# untitled.net
KiCad netlist of a schematic drawn in EAGLE
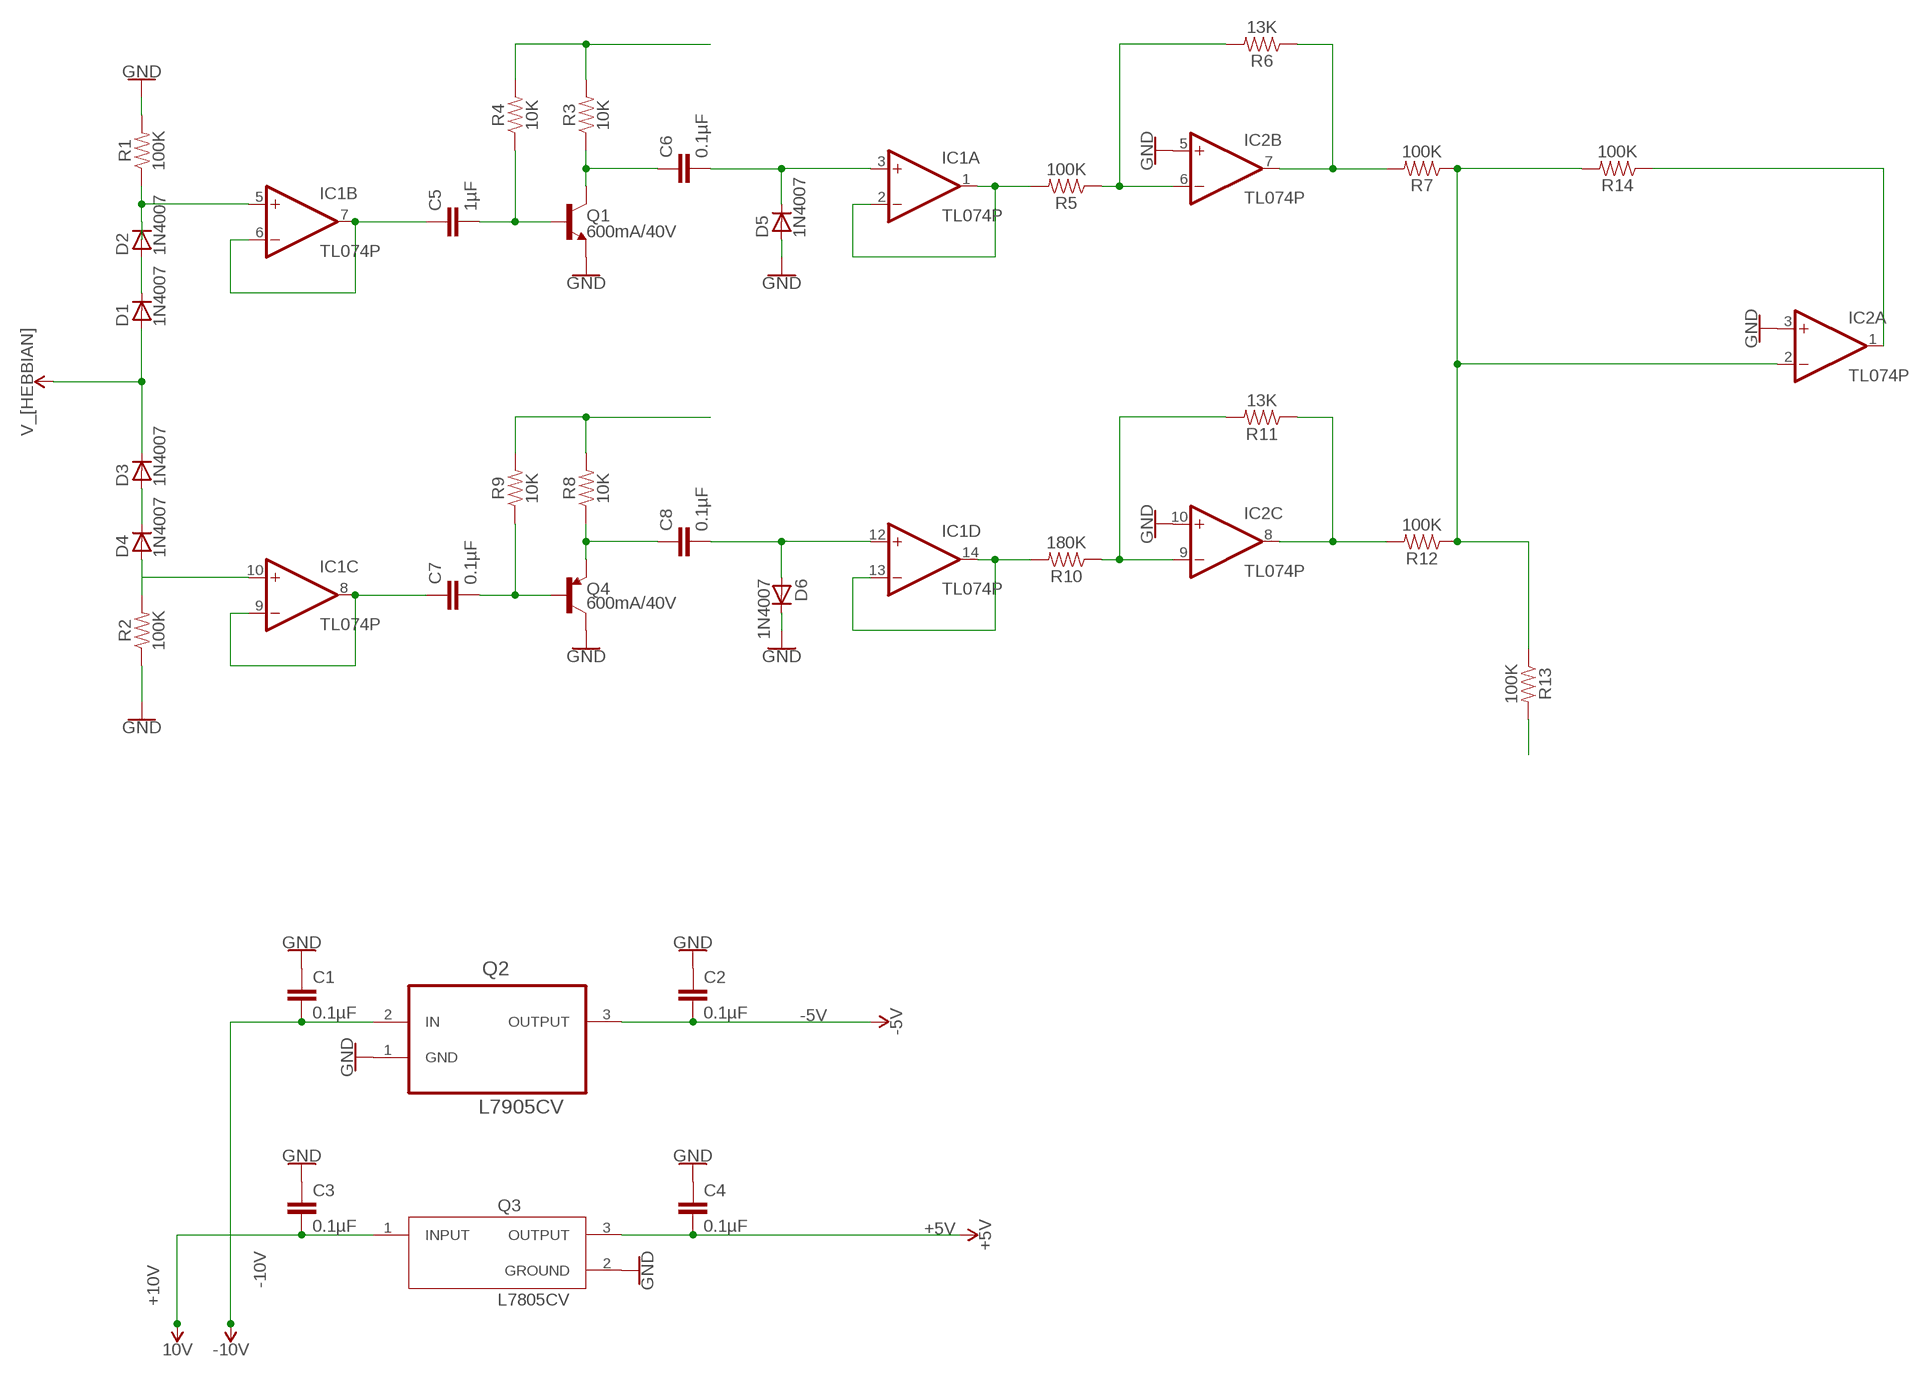
[diagram p0: schematic, sheet 1]

(export (version "E")
  (design (tool "Eeschema 10.0.6"))
  (components
    (comp (ref "C1")
      (value "0.1µF")
      (footprint "eagle-import:0805")
      (libsource (lib "eagle-import") (part "0.33UF/330NF-0805-50V-10%"))
    )
    (comp (ref "C2")
      (value "0.1µF")
      (footprint "eagle-import:0805")
      (libsource (lib "eagle-import") (part "0.33UF/330NF-0805-50V-10%"))
    )
    (comp (ref "C3")
      (value "0.1µF")
      (footprint "eagle-import:0805")
      (libsource (lib "eagle-import") (part "0.33UF/330NF-0805-50V-10%"))
    )
    (comp (ref "C4")
      (value "0.1µF")
      (footprint "eagle-import:0805")
      (libsource (lib "eagle-import") (part "0.33UF/330NF-0805-50V-10%"))
    )
    (comp (ref "C5")
      (value "1µF")
      (footprint "eagle-import:0805")
      (libsource (lib "eagle-import") (part "0.33UF/330NF-0805-50V-10%"))
    )
    (comp (ref "C6")
      (value "0.1µF")
      (footprint "eagle-import:0805")
      (libsource (lib "eagle-import") (part "0.33UF/330NF-0805-50V-10%"))
    )
    (comp (ref "C7")
      (value "0.1µF")
      (footprint "eagle-import:0805")
      (libsource (lib "eagle-import") (part "0.33UF/330NF-0805-50V-10%"))
    )
    (comp (ref "C8")
      (value "0.1µF")
      (footprint "eagle-import:0805")
      (libsource (lib "eagle-import") (part "0.33UF/330NF-0805-50V-10%"))
    )
    (comp (ref "D1")
      (value "1N4007")
      (footprint "eagle-import:SMA")
      (libsource (lib "eagle-import") (part "1N4007"))
    )
    (comp (ref "D2")
      (value "1N4007")
      (footprint "eagle-import:SMA")
      (libsource (lib "eagle-import") (part "1N4007"))
    )
    (comp (ref "D3")
      (value "1N4007")
      (footprint "eagle-import:SMA")
      (libsource (lib "eagle-import") (part "1N4007"))
    )
    (comp (ref "D4")
      (value "1N4007")
      (footprint "eagle-import:SMA")
      (libsource (lib "eagle-import") (part "1N4007"))
    )
    (comp (ref "D5")
      (value "1N4007")
      (footprint "eagle-import:SMA")
      (libsource (lib "eagle-import") (part "1N4007"))
    )
    (comp (ref "D6")
      (value "1N4007")
      (footprint "eagle-import:SMA")
      (libsource (lib "eagle-import") (part "1N4007"))
    )
    (comp (ref "IC1")
      (value "TL074P")
      (footprint "eagle-import:DIL14")
      (libsource (lib "eagle-import") (part "TL074P"))
    )
    (comp (ref "IC2")
      (value "TL074P")
      (footprint "eagle-import:DIL14")
      (libsource (lib "eagle-import") (part "TL074P"))
    )
    (comp (ref "Q1")
      (value "600mA/40V")
      (footprint "eagle-import:SOT23-3")
      (libsource (lib "eagle-import") (part "TRANS_NPN-MMBT2222AL"))
    )
    (comp (ref "Q2")
      (value "L7905CV")
      (footprint "eagle-import:TO254P450X1020X1935-3P")
      (fields (field (name "MF") "STMicroelectronics"))
      (libsource (lib "eagle-import") (part "L7905CV"))
    )
    (comp (ref "Q3")
      (value "L7805CV")
      (footprint "eagle-import:TO255P1040X460X1968-3")
      (fields (field (name "MF") "STMicroelectronics"))
      (libsource (lib "eagle-import") (part "L7805CV"))
    )
    (comp (ref "Q4")
      (value "600mA/40V")
      (footprint "eagle-import:SOT23-3")
      (libsource (lib "eagle-import") (part "TRANS_PNP-MMBT4403"))
    )
    (comp (ref "R1")
      (value "100K")
      (footprint "eagle-import:0805")
      (libsource (lib "eagle-import") (part "0.22OHM-0805-1/4W-1%"))
    )
    (comp (ref "R2")
      (value "100K")
      (footprint "eagle-import:0805")
      (libsource (lib "eagle-import") (part "0.22OHM-0805-1/4W-1%"))
    )
    (comp (ref "R3")
      (value "10K")
      (footprint "eagle-import:0805")
      (libsource (lib "eagle-import") (part "0.22OHM-0805-1/4W-1%"))
    )
    (comp (ref "R4")
      (value "10K")
      (footprint "eagle-import:0805")
      (libsource (lib "eagle-import") (part "0.22OHM-0805-1/4W-1%"))
    )
    (comp (ref "R5")
      (value "100K")
      (footprint "eagle-import:0805")
      (libsource (lib "eagle-import") (part "0.22OHM-0805-1/4W-1%"))
    )
    (comp (ref "R6")
      (value "13K")
      (footprint "eagle-import:0805")
      (libsource (lib "eagle-import") (part "0.22OHM-0805-1/4W-1%"))
    )
    (comp (ref "R7")
      (value "100K")
      (footprint "eagle-import:0805")
      (libsource (lib "eagle-import") (part "0.22OHM-0805-1/4W-1%"))
    )
    (comp (ref "R8")
      (value "10K")
      (footprint "eagle-import:0805")
      (libsource (lib "eagle-import") (part "0.22OHM-0805-1/4W-1%"))
    )
    (comp (ref "R9")
      (value "10K")
      (footprint "eagle-import:0805")
      (libsource (lib "eagle-import") (part "0.22OHM-0805-1/4W-1%"))
    )
    (comp (ref "R10")
      (value "180K")
      (footprint "eagle-import:0805")
      (libsource (lib "eagle-import") (part "0.22OHM-0805-1/4W-1%"))
    )
    (comp (ref "R11")
      (value "13K")
      (footprint "eagle-import:0805")
      (libsource (lib "eagle-import") (part "0.22OHM-0805-1/4W-1%"))
    )
    (comp (ref "R12")
      (value "100K")
      (footprint "eagle-import:0805")
      (libsource (lib "eagle-import") (part "0.22OHM-0805-1/4W-1%"))
    )
    (comp (ref "R13")
      (value "100K")
      (footprint "eagle-import:0805")
      (libsource (lib "eagle-import") (part "0.22OHM-0805-1/4W-1%"))
    )
    (comp (ref "R14")
      (value "100K")
      (footprint "eagle-import:0805")
      (libsource (lib "eagle-import") (part "0.22OHM-0805-1/4W-1%"))
    )
  )
  (nets
    (net (code "1") (name "+5V") (class "Default")
      (node (ref "C4") (pin "2") (pinfunction "2_2") (pintype "passive"))
      (node (ref "Q3") (pin "3") (pinfunction "OUTPUT_3") (pintype "output"))
    )
    (net (code "2") (name "-5V") (class "Default")
      (node (ref "C2") (pin "2") (pinfunction "2_2") (pintype "passive"))
      (node (ref "Q2") (pin "3") (pinfunction "OUTPUT_3") (pintype "output"))
    )
    (net (code "3") (name "-10V") (class "Default")
      (node (ref "C1") (pin "2") (pinfunction "2_2") (pintype "passive"))
      (node (ref "Q2") (pin "2") (pinfunction "IN_2") (pintype "input"))
    )
    (net (code "4") (name "10V") (class "Default")
      (node (ref "C3") (pin "2") (pinfunction "2_2") (pintype "passive"))
      (node (ref "Q3") (pin "1") (pinfunction "INPUT_1") (pintype "input"))
    )
    (net (code "5") (name "GND") (class "Default")
      (node (ref "C1") (pin "1") (pinfunction "1_1") (pintype "passive"))
      (node (ref "C2") (pin "1") (pinfunction "1_1") (pintype "passive"))
      (node (ref "C3") (pin "1") (pinfunction "1_1") (pintype "passive"))
      (node (ref "C4") (pin "1") (pinfunction "1_1") (pintype "passive"))
      (node (ref "D5") (pin "A") (pinfunction "A_A") (pintype "passive"))
      (node (ref "D6") (pin "K") (pinfunction "C_K") (pintype "passive"))
      (node (ref "IC2") (pin "10") (pinfunction "+IN_10") (pintype "input"))
      (node (ref "IC2") (pin "3") (pinfunction "+IN_3") (pintype "input"))
      (node (ref "IC2") (pin "5") (pinfunction "+IN_5") (pintype "input"))
      (node (ref "Q1") (pin "2") (pinfunction "E_2") (pintype "passive"))
      (node (ref "Q2") (pin "1") (pinfunction "GND_1") (pintype "passive"))
      (node (ref "Q3") (pin "2") (pinfunction "GROUND_2") (pintype "power_in"))
      (node (ref "Q4") (pin "3") (pinfunction "C_3") (pintype "passive"))
      (node (ref "R1") (pin "2") (pinfunction "2_2") (pintype "passive"))
      (node (ref "R2") (pin "1") (pinfunction "1_1") (pintype "passive"))
    )
    (net (code "6") (name "Net-(D1-C)") (class "Default")
      (node (ref "D1") (pin "K") (pinfunction "C_K") (pintype "passive"))
      (node (ref "D2") (pin "A") (pinfunction "A_A") (pintype "passive"))
    )
    (net (code "7") (name "Net-(D2-C)") (class "Default")
      (node (ref "D2") (pin "K") (pinfunction "C_K") (pintype "passive"))
      (node (ref "IC1") (pin "5") (pinfunction "+IN_5") (pintype "input"))
      (node (ref "R1") (pin "1") (pinfunction "1_1") (pintype "passive"))
    )
    (net (code "8") (name "Net-(D4-C)") (class "Default")
      (node (ref "D3") (pin "A") (pinfunction "A_A") (pintype "passive"))
      (node (ref "D4") (pin "K") (pinfunction "C_K") (pintype "passive"))
    )
    (net (code "9") (name "Net-(D4-PadA)") (class "Default")
      (node (ref "D4") (pin "A") (pinfunction "A_A") (pintype "passive"))
      (node (ref "R2") (pin "2") (pinfunction "2_2") (pintype "passive"))
    )
    (net (code "10") (name "Net-(D5-C)") (class "Default")
      (node (ref "C6") (pin "2") (pinfunction "2_2") (pintype "passive"))
      (node (ref "D5") (pin "K") (pinfunction "C_K") (pintype "passive"))
      (node (ref "IC1") (pin "3") (pinfunction "+IN_3") (pintype "input"))
    )
    (net (code "11") (name "Net-(IC1A--IN)") (class "Default")
      (node (ref "IC1") (pin "1") (pinfunction "OUT_1") (pintype "output"))
      (node (ref "IC1") (pin "2") (pinfunction "-IN_2") (pintype "input"))
      (node (ref "R5") (pin "2") (pinfunction "2_2") (pintype "passive"))
    )
    (net (code "12") (name "Net-(IC1B--IN)") (class "Default")
      (node (ref "C5") (pin "1") (pinfunction "1_1") (pintype "passive"))
      (node (ref "IC1") (pin "6") (pinfunction "-IN_6") (pintype "input"))
      (node (ref "IC1") (pin "7") (pinfunction "OUT_7") (pintype "output"))
    )
    (net (code "13") (name "Net-(IC1C--IN)") (class "Default")
      (node (ref "C7") (pin "1") (pinfunction "1_1") (pintype "passive"))
      (node (ref "IC1") (pin "8") (pinfunction "OUT_8") (pintype "output"))
      (node (ref "IC1") (pin "9") (pinfunction "-IN_9") (pintype "input"))
    )
    (net (code "14") (name "Net-(IC1D-+IN)") (class "Default")
      (node (ref "C8") (pin "2") (pinfunction "2_2") (pintype "passive"))
      (node (ref "D6") (pin "A") (pinfunction "A_A") (pintype "passive"))
      (node (ref "IC1") (pin "12") (pinfunction "+IN_12") (pintype "input"))
    )
    (net (code "15") (name "Net-(IC1D--IN)") (class "Default")
      (node (ref "IC1") (pin "13") (pinfunction "-IN_13") (pintype "input"))
      (node (ref "IC1") (pin "14") (pinfunction "OUT_14") (pintype "output"))
      (node (ref "R10") (pin "2") (pinfunction "2_2") (pintype "passive"))
    )
    (net (code "16") (name "Net-(IC2A--IN)") (class "Default")
      (node (ref "IC2") (pin "2") (pinfunction "-IN_2") (pintype "input"))
      (node (ref "R12") (pin "1") (pinfunction "1_1") (pintype "passive"))
      (node (ref "R13") (pin "1") (pinfunction "1_1") (pintype "passive"))
      (node (ref "R14") (pin "2") (pinfunction "2_2") (pintype "passive"))
      (node (ref "R7") (pin "1") (pinfunction "1_1") (pintype "passive"))
    )
    (net (code "17") (name "Net-(IC2A-OUT)") (class "Default")
      (node (ref "IC2") (pin "1") (pinfunction "OUT_1") (pintype "output"))
      (node (ref "R14") (pin "1") (pinfunction "1_1") (pintype "passive"))
    )
    (net (code "18") (name "Net-(IC2B--IN)") (class "Default")
      (node (ref "IC2") (pin "6") (pinfunction "-IN_6") (pintype "input"))
      (node (ref "R5") (pin "1") (pinfunction "1_1") (pintype "passive"))
      (node (ref "R6") (pin "2") (pinfunction "2_2") (pintype "passive"))
    )
    (net (code "19") (name "Net-(IC2B-OUT)") (class "Default")
      (node (ref "IC2") (pin "7") (pinfunction "OUT_7") (pintype "output"))
      (node (ref "R6") (pin "1") (pinfunction "1_1") (pintype "passive"))
      (node (ref "R7") (pin "2") (pinfunction "2_2") (pintype "passive"))
    )
    (net (code "20") (name "Net-(IC2C--IN)") (class "Default")
      (node (ref "IC2") (pin "9") (pinfunction "-IN_9") (pintype "input"))
      (node (ref "R10") (pin "1") (pinfunction "1_1") (pintype "passive"))
      (node (ref "R11") (pin "2") (pinfunction "2_2") (pintype "passive"))
    )
    (net (code "21") (name "Net-(IC2C-OUT)") (class "Default")
      (node (ref "IC2") (pin "8") (pinfunction "OUT_8") (pintype "output"))
      (node (ref "R11") (pin "1") (pinfunction "1_1") (pintype "passive"))
      (node (ref "R12") (pin "2") (pinfunction "2_2") (pintype "passive"))
    )
    (net (code "22") (name "Net-(Q1-B)") (class "Default")
      (node (ref "C5") (pin "2") (pinfunction "2_2") (pintype "passive"))
      (node (ref "Q1") (pin "1") (pinfunction "B_1") (pintype "passive"))
      (node (ref "R4") (pin "1") (pinfunction "1_1") (pintype "passive"))
    )
    (net (code "23") (name "Net-(Q1-C)") (class "Default")
      (node (ref "C6") (pin "1") (pinfunction "1_1") (pintype "passive"))
      (node (ref "Q1") (pin "3") (pinfunction "C_3") (pintype "passive"))
      (node (ref "R3") (pin "1") (pinfunction "1_1") (pintype "passive"))
    )
    (net (code "24") (name "Net-(Q4-B)") (class "Default")
      (node (ref "C7") (pin "2") (pinfunction "2_2") (pintype "passive"))
      (node (ref "Q4") (pin "1") (pinfunction "B_1") (pintype "passive"))
      (node (ref "R9") (pin "1") (pinfunction "1_1") (pintype "passive"))
    )
    (net (code "25") (name "Net-(Q4-E)") (class "Default")
      (node (ref "C8") (pin "1") (pinfunction "1_1") (pintype "passive"))
      (node (ref "Q4") (pin "2") (pinfunction "E_2") (pintype "passive"))
      (node (ref "R8") (pin "1") (pinfunction "1_1") (pintype "passive"))
    )
    (net (code "26") (name "Net-(R3-Pad2)") (class "Default")
      (node (ref "R3") (pin "2") (pinfunction "2_2") (pintype "passive"))
      (node (ref "R4") (pin "2") (pinfunction "2_2") (pintype "passive"))
    )
    (net (code "27") (name "Net-(R8-Pad2)") (class "Default")
      (node (ref "R8") (pin "2") (pinfunction "2_2") (pintype "passive"))
      (node (ref "R9") (pin "2") (pinfunction "2_2") (pintype "passive"))
    )
    (net (code "28") (name "V_[HEBBIAN]") (class "Default")
      (node (ref "D1") (pin "A") (pinfunction "A_A") (pintype "passive"))
      (node (ref "D3") (pin "K") (pinfunction "C_K") (pintype "passive"))
    )
    (net (code "29") (name "unconnected-(IC1C-+IN-Pad10)") (class "Default")
      (node (ref "IC1") (pin "10") (pinfunction "+IN_10") (pintype "input"))
    )
    (net (code "30") (name "unconnected-(R13-Pad2)") (class "Default")
      (node (ref "R13") (pin "2") (pinfunction "2_2") (pintype "passive"))
    )
  )
)
